# Forehead_Module.net
KiCad netlist of a schematic drawn in Altium Designer
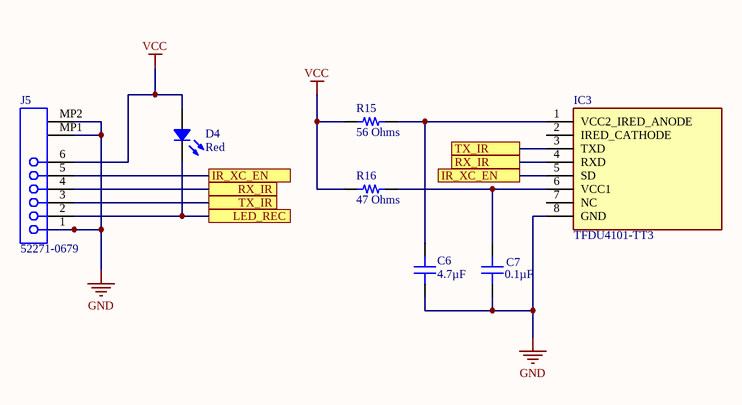
[diagram p0: Forehead Module.SchDoc]

(export (version "E")
  (design (tool "Eeschema 10.0.6"))
  (components
    (comp (ref "C6")
      (value "4.7µF")
      (footprint "CAP 1210_3225 - 2.8MM")
      (description "CAP CER 4.7UF 50V X7R 1210")
      (fields (field (name "PART NUMBER") "UMK325B7475KM-T") (field (name "MANUFACTURER") "Taiyo Yuden"))
      (libsource (lib "Celestial Altium Library - altium_library") (part "Capacitor"))
    )
    (comp (ref "C7")
      (value "0.1µF")
      (footprint "CAP 0603_1608")
      (description "CAP CER 0.1UF 50V X7R 0603")
      (fields (field (name "PART NUMBER") "C0603C104K5RAC7411") (field (name "MANUFACTURER") "KEMET"))
      (libsource (lib "Celestial Altium Library - altium_library") (part "Capacitor"))
    )
    (comp (ref "D4")
      (value "Red")
      (footprint "LED 1206_3216 RED")
      (description "LED RED DIFFUSED 1206 SMD")
      (fields
        (field (name "PART NUMBER") "SML-LX1206IW-TR")
        (field (name "MANUFACTURER") "Lumex Opto/Components Inc.")
      )
      (libsource (lib "Celestial Altium Library - altium_library") (part "LED"))
    )
    (comp (ref "IC3")
      (value "TFDU4101-TT3")
      (footprint "SamacSys:TFDU4101-TR3")
      (description "Integrated Circuit")
      (fields (field (name "MOUSER PART NUMBER") "782-TFDU4101-TT3"))
      (libsource (lib "SamacSys") (part "TFDU4101-TT3"))
    )
    (comp (ref "J5")
      (value "52271-0679")
      (footprint "MOLX-52271-0679")
      (fields (field (name "MANUFACTURER") "Molex"))
      (libsource (lib "Molex FFC - FPC Connectors (SMT)") (part "52271-0679"))
    )
    (comp (ref "R15")
      (value "56 Ohms")
      (footprint "RES 0603_1608")
      (description "RES SMD 56 OHM 1% 1/4W 0603")
      (fields
        (field (name "PART NUMBER") "ERJ-PA3F56R0V")
        (field (name "MANUFACTURER") "Panasonic Electronic Components")
      )
      (libsource (lib "Celestial Altium Library - altium_library") (part "Resistor"))
    )
    (comp (ref "R16")
      (value "47 Ohms")
      (footprint "RES 0603_1608")
      (description "RES SMD 47 OHM 1% 1/4W 0603")
      (fields (field (name "PART NUMBER") "RCS060347R0FKEA") (field (name "MANUFACTURER") "Vishay Dale"))
      (libsource (lib "Celestial Altium Library - altium_library") (part "Resistor"))
    )
  )
  (nets
    (net (code "1") (name "/IR_XC_EN") (class "Default")
      (node (ref "IC3") (pin "5") (pinfunction "SD_5") (pintype "passive"))
      (node (ref "J5") (pin "5") (pinfunction "5_5") (pintype "passive"))
    )
    (net (code "2") (name "/LED_REC") (class "Default")
      (node (ref "D4") (pin "2") (pinfunction "2_2") (pintype "passive"))
      (node (ref "J5") (pin "2") (pinfunction "2_2") (pintype "passive"))
    )
    (net (code "3") (name "/RX_IR") (class "Default")
      (node (ref "IC3") (pin "4") (pinfunction "RXD_4") (pintype "passive"))
      (node (ref "J5") (pin "4") (pinfunction "4_4") (pintype "passive"))
    )
    (net (code "4") (name "/TX_IR") (class "Default")
      (node (ref "IC3") (pin "3") (pinfunction "TXD_3") (pintype "passive"))
      (node (ref "J5") (pin "3") (pinfunction "3_3") (pintype "passive"))
    )
    (net (code "5") (name "GND") (class "Default")
      (node (ref "C6") (pin "1") (pinfunction "1_1") (pintype "passive"))
      (node (ref "C7") (pin "1") (pinfunction "1_1") (pintype "passive"))
      (node (ref "IC3") (pin "8") (pinfunction "GND_8") (pintype "passive"))
      (node (ref "J5") (pin "1") (pinfunction "1_1") (pintype "passive"))
      (node (ref "J5") (pin "MP1") (pinfunction "MP1_MP1") (pintype "passive"))
      (node (ref "J5") (pin "MP2") (pinfunction "MP2_MP2") (pintype "passive"))
    )
    (net (code "6") (name "Net-(IC3-VCC1)") (class "Default")
      (node (ref "C7") (pin "2") (pinfunction "2_2") (pintype "passive"))
      (node (ref "IC3") (pin "6") (pinfunction "VCC1_6") (pintype "passive"))
      (node (ref "R16") (pin "2") (pinfunction "2_2") (pintype "passive"))
    )
    (net (code "7") (name "Net-(IC3-VCC2_IRED_ANODE)") (class "Default")
      (node (ref "C6") (pin "2") (pinfunction "2_2") (pintype "passive"))
      (node (ref "IC3") (pin "1") (pinfunction "VCC2_IRED_ANODE_1") (pintype "passive"))
      (node (ref "R15") (pin "2") (pinfunction "2_2") (pintype "passive"))
    )
    (net (code "8") (name "VCC") (class "Default")
      (node (ref "D4") (pin "1") (pinfunction "1_1") (pintype "passive"))
      (node (ref "J5") (pin "6") (pinfunction "6_6") (pintype "passive"))
      (node (ref "R15") (pin "1") (pinfunction "1_1") (pintype "passive"))
      (node (ref "R16") (pin "1") (pinfunction "1_1") (pintype "passive"))
    )
    (net (code "9") (name "unconnected-(IC3-IRED_CATHODE-Pad2)") (class "Default")
      (node (ref "IC3") (pin "2") (pinfunction "IRED_CATHODE_2") (pintype "passive"))
    )
    (net (code "10") (name "unconnected-(IC3-NC-Pad7)") (class "Default")
      (node (ref "IC3") (pin "7") (pinfunction "NC_7") (pintype "passive"))
    )
  )
)
